# design.net
KiCad netlist of a schematic drawn in Altium Designer
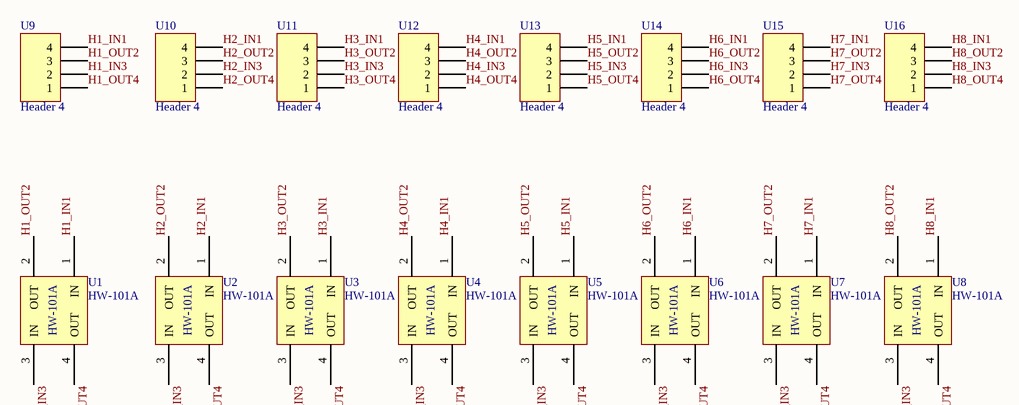
[diagram p0: 检测板.SchDoc]

(export (version "E")
  (design (tool "Eeschema 10.0.6"))
  (components
    (comp (ref "U1") (value "HW-101A") (footprint "SOT-23-4") (libsource (lib "磁导航") (part "HW-101A")))
    (comp (ref "U2") (value "HW-101A") (footprint "SOT-23-4") (libsource (lib "磁导航") (part "HW-101A")))
    (comp (ref "U3") (value "HW-101A") (footprint "SOT-23-4") (libsource (lib "磁导航") (part "HW-101A")))
    (comp (ref "U4") (value "HW-101A") (footprint "SOT-23-4") (libsource (lib "磁导航") (part "HW-101A")))
    (comp (ref "U5") (value "HW-101A") (footprint "SOT-23-4") (libsource (lib "磁导航") (part "HW-101A")))
    (comp (ref "U6") (value "HW-101A") (footprint "SOT-23-4") (libsource (lib "磁导航") (part "HW-101A")))
    (comp (ref "U7") (value "HW-101A") (footprint "SOT-23-4") (libsource (lib "磁导航") (part "HW-101A")))
    (comp (ref "U8") (value "HW-101A") (footprint "SOT-23-4") (libsource (lib "磁导航") (part "HW-101A")))
    (comp (ref "U9")
      (value "Header 4")
      (footprint "PIN4")
      (description "Header, 4-Pin")
      (fields (field (name "PUBLISHER") "Altium Limited"))
      (libsource (lib "Miscellaneous Connectors") (part "Header 4"))
    )
    (comp (ref "U10")
      (value "Header 4")
      (footprint "PIN4")
      (description "Header, 4-Pin")
      (fields (field (name "PUBLISHER") "Altium Limited"))
      (libsource (lib "Miscellaneous Connectors") (part "Header 4"))
    )
    (comp (ref "U11")
      (value "Header 4")
      (footprint "PIN4")
      (description "Header, 4-Pin")
      (fields (field (name "PUBLISHER") "Altium Limited"))
      (libsource (lib "Miscellaneous Connectors") (part "Header 4"))
    )
    (comp (ref "U12")
      (value "Header 4")
      (footprint "PIN4")
      (description "Header, 4-Pin")
      (fields (field (name "PUBLISHER") "Altium Limited"))
      (libsource (lib "Miscellaneous Connectors") (part "Header 4"))
    )
    (comp (ref "U13")
      (value "Header 4")
      (footprint "PIN4")
      (description "Header, 4-Pin")
      (fields (field (name "PUBLISHER") "Altium Limited"))
      (libsource (lib "Miscellaneous Connectors") (part "Header 4"))
    )
    (comp (ref "U14")
      (value "Header 4")
      (footprint "PIN4")
      (description "Header, 4-Pin")
      (fields (field (name "PUBLISHER") "Altium Limited"))
      (libsource (lib "Miscellaneous Connectors") (part "Header 4"))
    )
    (comp (ref "U15")
      (value "Header 4")
      (footprint "PIN4")
      (description "Header, 4-Pin")
      (fields (field (name "PUBLISHER") "Altium Limited"))
      (libsource (lib "Miscellaneous Connectors") (part "Header 4"))
    )
    (comp (ref "U16")
      (value "Header 4")
      (footprint "PIN4")
      (description "Header, 4-Pin")
      (fields (field (name "PUBLISHER") "Altium Limited"))
      (libsource (lib "Miscellaneous Connectors") (part "Header 4"))
    )
  )
  (nets
    (net (code "1") (name "/H1_IN1") (class "Default")
      (node (ref "U1") (pin "1") (pinfunction "IN_1") (pintype "passive"))
      (node (ref "U9") (pin "4") (pinfunction "4_4") (pintype "passive"))
    )
    (net (code "2") (name "/H1_IN3") (class "Default")
      (node (ref "U1") (pin "3") (pinfunction "IN_3") (pintype "passive"))
      (node (ref "U9") (pin "2") (pinfunction "2_2") (pintype "passive"))
    )
    (net (code "3") (name "/H1_OUT2") (class "Default")
      (node (ref "U1") (pin "2") (pinfunction "OUT_2") (pintype "passive"))
      (node (ref "U9") (pin "3") (pinfunction "3_3") (pintype "passive"))
    )
    (net (code "4") (name "/H1_OUT4") (class "Default")
      (node (ref "U1") (pin "4") (pinfunction "OUT_4") (pintype "passive"))
      (node (ref "U9") (pin "1") (pinfunction "1_1") (pintype "passive"))
    )
    (net (code "5") (name "/H2_IN1") (class "Default")
      (node (ref "U10") (pin "4") (pinfunction "4_4") (pintype "passive"))
      (node (ref "U2") (pin "1") (pinfunction "IN_1") (pintype "passive"))
    )
    (net (code "6") (name "/H2_IN3") (class "Default")
      (node (ref "U10") (pin "2") (pinfunction "2_2") (pintype "passive"))
      (node (ref "U2") (pin "3") (pinfunction "IN_3") (pintype "passive"))
    )
    (net (code "7") (name "/H2_OUT2") (class "Default")
      (node (ref "U10") (pin "3") (pinfunction "3_3") (pintype "passive"))
      (node (ref "U2") (pin "2") (pinfunction "OUT_2") (pintype "passive"))
    )
    (net (code "8") (name "/H2_OUT4") (class "Default")
      (node (ref "U10") (pin "1") (pinfunction "1_1") (pintype "passive"))
      (node (ref "U2") (pin "4") (pinfunction "OUT_4") (pintype "passive"))
    )
    (net (code "9") (name "/H3_IN1") (class "Default")
      (node (ref "U11") (pin "4") (pinfunction "4_4") (pintype "passive"))
      (node (ref "U3") (pin "1") (pinfunction "IN_1") (pintype "passive"))
    )
    (net (code "10") (name "/H3_IN3") (class "Default")
      (node (ref "U11") (pin "2") (pinfunction "2_2") (pintype "passive"))
      (node (ref "U3") (pin "3") (pinfunction "IN_3") (pintype "passive"))
    )
    (net (code "11") (name "/H3_OUT2") (class "Default")
      (node (ref "U11") (pin "3") (pinfunction "3_3") (pintype "passive"))
      (node (ref "U3") (pin "2") (pinfunction "OUT_2") (pintype "passive"))
    )
    (net (code "12") (name "/H3_OUT4") (class "Default")
      (node (ref "U11") (pin "1") (pinfunction "1_1") (pintype "passive"))
      (node (ref "U3") (pin "4") (pinfunction "OUT_4") (pintype "passive"))
    )
    (net (code "13") (name "/H4_IN1") (class "Default")
      (node (ref "U12") (pin "4") (pinfunction "4_4") (pintype "passive"))
      (node (ref "U4") (pin "1") (pinfunction "IN_1") (pintype "passive"))
    )
    (net (code "14") (name "/H4_IN3") (class "Default")
      (node (ref "U12") (pin "2") (pinfunction "2_2") (pintype "passive"))
      (node (ref "U4") (pin "3") (pinfunction "IN_3") (pintype "passive"))
    )
    (net (code "15") (name "/H4_OUT2") (class "Default")
      (node (ref "U12") (pin "3") (pinfunction "3_3") (pintype "passive"))
      (node (ref "U4") (pin "2") (pinfunction "OUT_2") (pintype "passive"))
    )
    (net (code "16") (name "/H4_OUT4") (class "Default")
      (node (ref "U12") (pin "1") (pinfunction "1_1") (pintype "passive"))
      (node (ref "U4") (pin "4") (pinfunction "OUT_4") (pintype "passive"))
    )
    (net (code "17") (name "/H5_IN1") (class "Default")
      (node (ref "U13") (pin "4") (pinfunction "4_4") (pintype "passive"))
      (node (ref "U5") (pin "1") (pinfunction "IN_1") (pintype "passive"))
    )
    (net (code "18") (name "/H5_IN3") (class "Default")
      (node (ref "U13") (pin "2") (pinfunction "2_2") (pintype "passive"))
      (node (ref "U5") (pin "3") (pinfunction "IN_3") (pintype "passive"))
    )
    (net (code "19") (name "/H5_OUT2") (class "Default")
      (node (ref "U13") (pin "3") (pinfunction "3_3") (pintype "passive"))
      (node (ref "U5") (pin "2") (pinfunction "OUT_2") (pintype "passive"))
    )
    (net (code "20") (name "/H5_OUT4") (class "Default")
      (node (ref "U13") (pin "1") (pinfunction "1_1") (pintype "passive"))
      (node (ref "U5") (pin "4") (pinfunction "OUT_4") (pintype "passive"))
    )
    (net (code "21") (name "/H6_IN1") (class "Default")
      (node (ref "U14") (pin "4") (pinfunction "4_4") (pintype "passive"))
      (node (ref "U6") (pin "1") (pinfunction "IN_1") (pintype "passive"))
    )
    (net (code "22") (name "/H6_IN3") (class "Default")
      (node (ref "U14") (pin "2") (pinfunction "2_2") (pintype "passive"))
      (node (ref "U6") (pin "3") (pinfunction "IN_3") (pintype "passive"))
    )
    (net (code "23") (name "/H6_OUT2") (class "Default")
      (node (ref "U14") (pin "3") (pinfunction "3_3") (pintype "passive"))
      (node (ref "U6") (pin "2") (pinfunction "OUT_2") (pintype "passive"))
    )
    (net (code "24") (name "/H6_OUT4") (class "Default")
      (node (ref "U14") (pin "1") (pinfunction "1_1") (pintype "passive"))
      (node (ref "U6") (pin "4") (pinfunction "OUT_4") (pintype "passive"))
    )
    (net (code "25") (name "/H7_IN1") (class "Default")
      (node (ref "U15") (pin "4") (pinfunction "4_4") (pintype "passive"))
      (node (ref "U7") (pin "1") (pinfunction "IN_1") (pintype "passive"))
    )
    (net (code "26") (name "/H7_IN3") (class "Default")
      (node (ref "U15") (pin "2") (pinfunction "2_2") (pintype "passive"))
      (node (ref "U7") (pin "3") (pinfunction "IN_3") (pintype "passive"))
    )
    (net (code "27") (name "/H7_OUT2") (class "Default")
      (node (ref "U15") (pin "3") (pinfunction "3_3") (pintype "passive"))
      (node (ref "U7") (pin "2") (pinfunction "OUT_2") (pintype "passive"))
    )
    (net (code "28") (name "/H7_OUT4") (class "Default")
      (node (ref "U15") (pin "1") (pinfunction "1_1") (pintype "passive"))
      (node (ref "U7") (pin "4") (pinfunction "OUT_4") (pintype "passive"))
    )
    (net (code "29") (name "/H8_IN1") (class "Default")
      (node (ref "U16") (pin "4") (pinfunction "4_4") (pintype "passive"))
      (node (ref "U8") (pin "1") (pinfunction "IN_1") (pintype "passive"))
    )
    (net (code "30") (name "/H8_IN3") (class "Default")
      (node (ref "U16") (pin "2") (pinfunction "2_2") (pintype "passive"))
      (node (ref "U8") (pin "3") (pinfunction "IN_3") (pintype "passive"))
    )
    (net (code "31") (name "/H8_OUT2") (class "Default")
      (node (ref "U16") (pin "3") (pinfunction "3_3") (pintype "passive"))
      (node (ref "U8") (pin "2") (pinfunction "OUT_2") (pintype "passive"))
    )
    (net (code "32") (name "/H8_OUT4") (class "Default")
      (node (ref "U16") (pin "1") (pinfunction "1_1") (pintype "passive"))
      (node (ref "U8") (pin "4") (pinfunction "OUT_4") (pintype "passive"))
    )
  )
)
